# programming_header.net
KiCad netlist of a schematic drawn in Altium Designer
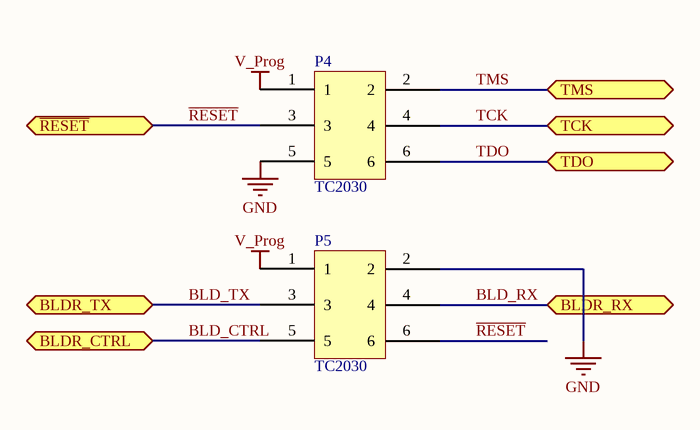
[diagram p0: programming_header.SchDoc]

(export (version "E")
  (design (tool "Eeschema 10.0.6"))
  (components
    (comp (ref "P4")
      (value "TC2030")
      (footprint "TC2030-IDC-NLFP")
      (description "TC2030-MCP-NL")
      (libsource (lib "connectors") (part "TC2030"))
    )
    (comp (ref "P5")
      (value "TC2030")
      (footprint "TC2030-IDC-NLFP")
      (description "TC2030-MCP-NL")
      (libsource (lib "connectors") (part "TC2030"))
    )
  )
  (nets
    (net (code "1") (name "/BLD_CTRL") (class "Default")
      (node (ref "P5") (pin "5") (pinfunction "5_5") (pintype "passive"))
    )
    (net (code "2") (name "/BLD_RX") (class "Default")
      (node (ref "P5") (pin "4") (pinfunction "4_4") (pintype "passive"))
    )
    (net (code "3") (name "/BLD_TX") (class "Default")
      (node (ref "P5") (pin "3") (pinfunction "3_3") (pintype "passive"))
    )
    (net (code "4") (name "/TCK") (class "Default")
      (node (ref "P4") (pin "4") (pinfunction "4_4") (pintype "passive"))
    )
    (net (code "5") (name "/TDO") (class "Default")
      (node (ref "P4") (pin "6") (pinfunction "6_6") (pintype "passive"))
    )
    (net (code "6") (name "/TMS") (class "Default")
      (node (ref "P4") (pin "2") (pinfunction "2_2") (pintype "passive"))
    )
    (net (code "7") (name "/~{RESET}") (class "Default")
      (node (ref "P4") (pin "3") (pinfunction "3_3") (pintype "passive"))
      (node (ref "P5") (pin "6") (pinfunction "6_6") (pintype "passive"))
    )
    (net (code "8") (name "GND") (class "Default")
      (node (ref "P4") (pin "5") (pinfunction "5_5") (pintype "passive"))
      (node (ref "P5") (pin "2") (pinfunction "2_2") (pintype "passive"))
    )
    (net (code "9") (name "V_Prog") (class "Default")
      (node (ref "P4") (pin "1") (pinfunction "1_1") (pintype "passive"))
      (node (ref "P5") (pin "1") (pinfunction "1_1") (pintype "passive"))
    )
  )
)
